# relay_latch_circuit_A.net
KiCad netlist of a schematic drawn in Altium Designer
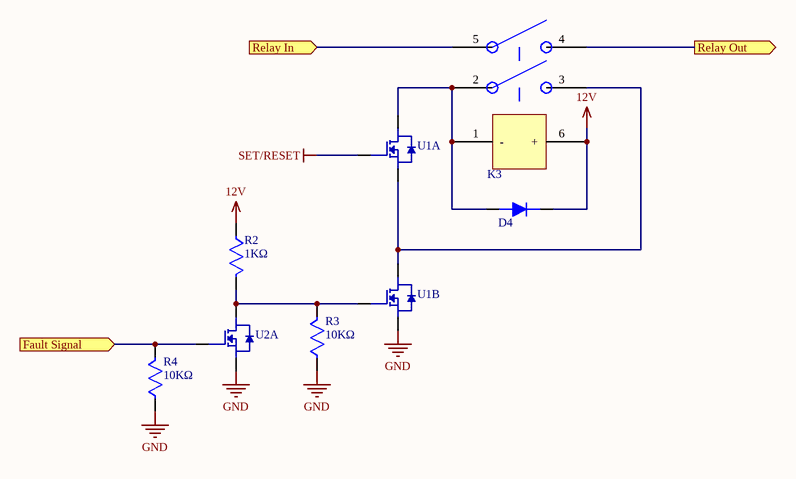
[diagram p0: relay_latch_circuit_A.SchDoc]

(export (version "E")
  (design (tool "Eeschema 10.0.6"))
  (components
    (comp (ref "D4")
      (value "SD560BTR")
      (footprint "DIODE")
      (description "DIODE GEN PURP 600V 5A SMB")
      (fields (field (name "MANUFACTURER") "SMC"))
      (libsource (lib "sdc_prech_schlib") (part "SD560BTR"))
    )
    (comp (ref "K3")
      (value "5-1419124-6")
      (footprint "DPST SDC RELAY")
      (description "General Purpose Relay, Osa Series, Power, Non Latching, Dpst-No, 12 Vdc, 3 A Rohs Compliant: Yes")
      (fields (field (name "MANUFACTURER") "TE Connectivity"))
      (libsource (lib "sdc_prech_schlib") (part "5-1419124-6"))
    )
    (comp (ref "R2")
      (value "1KΩ")
      (footprint "RESISTOR CRCW0603")
      (description "RES SMD 1K OHM 1% 1/10W 0603")
      (fields
        (field (name "MANUFACTURER") "Vishay Dale")
        (field (name "MANUFACTURER PART NUMBER") "CRCW06031K00FKEA")
      )
      (libsource (lib "sdc_prech_schlib") (part "CRCW06031K00FKEA"))
    )
    (comp (ref "R3")
      (value "10KΩ")
      (footprint "RESISTOR CRCW0603")
      (description "RES SMD 10K OHM 1% 1/10W 0603")
      (fields
        (field (name "MANUFACTURER") "Vishay")
        (field (name "MANUFACTURER PART NUMBER") "CRCW060310K0FKEA")
      )
      (libsource (lib "sdc_prech_schlib") (part "CRCW060310K0FKEA"))
    )
    (comp (ref "R4")
      (value "10KΩ")
      (footprint "RESISTOR CRCW0603")
      (description "RES SMD 10K OHM 1% 1/10W 0603")
      (fields
        (field (name "MANUFACTURER") "Vishay")
        (field (name "MANUFACTURER PART NUMBER") "CRCW060310K0FKEA")
      )
      (libsource (lib "sdc_prech_schlib") (part "CRCW060310K0FKEA"))
    )
    (comp (ref "U1")
      (value "SSM6N7002CFU,LF")
      (footprint "N-MOSFET (2 FETS)")
      (description "MOSFET 2N-CH 60V 0.17A US6")
      (fields (field (name "MANUFACTURER") "Toshiba"))
      (libsource (lib "sdc_prech_schlib") (part "SSM6N7002CFU,LF"))
    )
    (comp (ref "U2")
      (value "SSM6N7002CFU,LF")
      (footprint "N-MOSFET (2 FETS)")
      (description "MOSFET 2N-CH 60V 0.17A US6")
      (fields (field (name "MANUFACTURER") "Toshiba"))
      (libsource (lib "sdc_prech_schlib") (part "SSM6N7002CFU,LF"))
    )
  )
  (nets
    (net (code "1") (name "/Fault Signal") (class "Default")
      (node (ref "R4") (pin "2") (pinfunction "2_2") (pintype "passive"))
      (node (ref "U2") (pin "2") (pinfunction "G1_2") (pintype "passive"))
    )
    (net (code "2") (name "/Relay In") (class "Default") (node (ref "K3") (pin "5") (pintype "passive")))
    (net (code "3") (name "/Relay Out") (class "Default") (node (ref "K3") (pin "4") (pintype "passive")))
    (net (code "4") (name "12V") (class "Default")
      (node (ref "D4") (pin "2") (pinfunction "2_2") (pintype "passive"))
      (node (ref "K3") (pin "6") (pinfunction "+_6") (pintype "passive"))
      (node (ref "R2") (pin "1") (pinfunction "1_1") (pintype "passive"))
    )
    (net (code "5") (name "GND") (class "Default")
      (node (ref "R3") (pin "1") (pinfunction "1_1") (pintype "passive"))
      (node (ref "R4") (pin "1") (pinfunction "1_1") (pintype "passive"))
      (node (ref "U1") (pin "4") (pinfunction "S2_4") (pintype "passive"))
      (node (ref "U2") (pin "1") (pinfunction "S1_1") (pintype "passive"))
    )
    (net (code "6") (name "Net-(K3--)") (class "Default")
      (node (ref "D4") (pin "1") (pinfunction "1_1") (pintype "passive"))
      (node (ref "K3") (pin "1") (pinfunction "-_1") (pintype "passive"))
      (node (ref "K3") (pin "2") (pintype "passive"))
      (node (ref "U1") (pin "6") (pinfunction "D1_6") (pintype "passive"))
    )
    (net (code "7") (name "Net-(U1A-S1)") (class "Default")
      (node (ref "K3") (pin "3") (pintype "passive"))
      (node (ref "U1") (pin "1") (pinfunction "S1_1") (pintype "passive"))
      (node (ref "U1") (pin "3") (pinfunction "D2_3") (pintype "passive"))
    )
    (net (code "8") (name "Net-(U1B-G2)") (class "Default")
      (node (ref "R2") (pin "2") (pinfunction "2_2") (pintype "passive"))
      (node (ref "R3") (pin "2") (pinfunction "2_2") (pintype "passive"))
      (node (ref "U1") (pin "5") (pinfunction "G2_5") (pintype "passive"))
      (node (ref "U2") (pin "6") (pinfunction "D1_6") (pintype "passive"))
    )
    (net (code "9") (name "SET{slash}RESET") (class "Default")
      (node (ref "U1") (pin "2") (pinfunction "G1_2") (pintype "passive"))
    )
  )
)
